# 05_POWER_MCU_1.net
KiCad netlist of a schematic drawn in Altium Designer
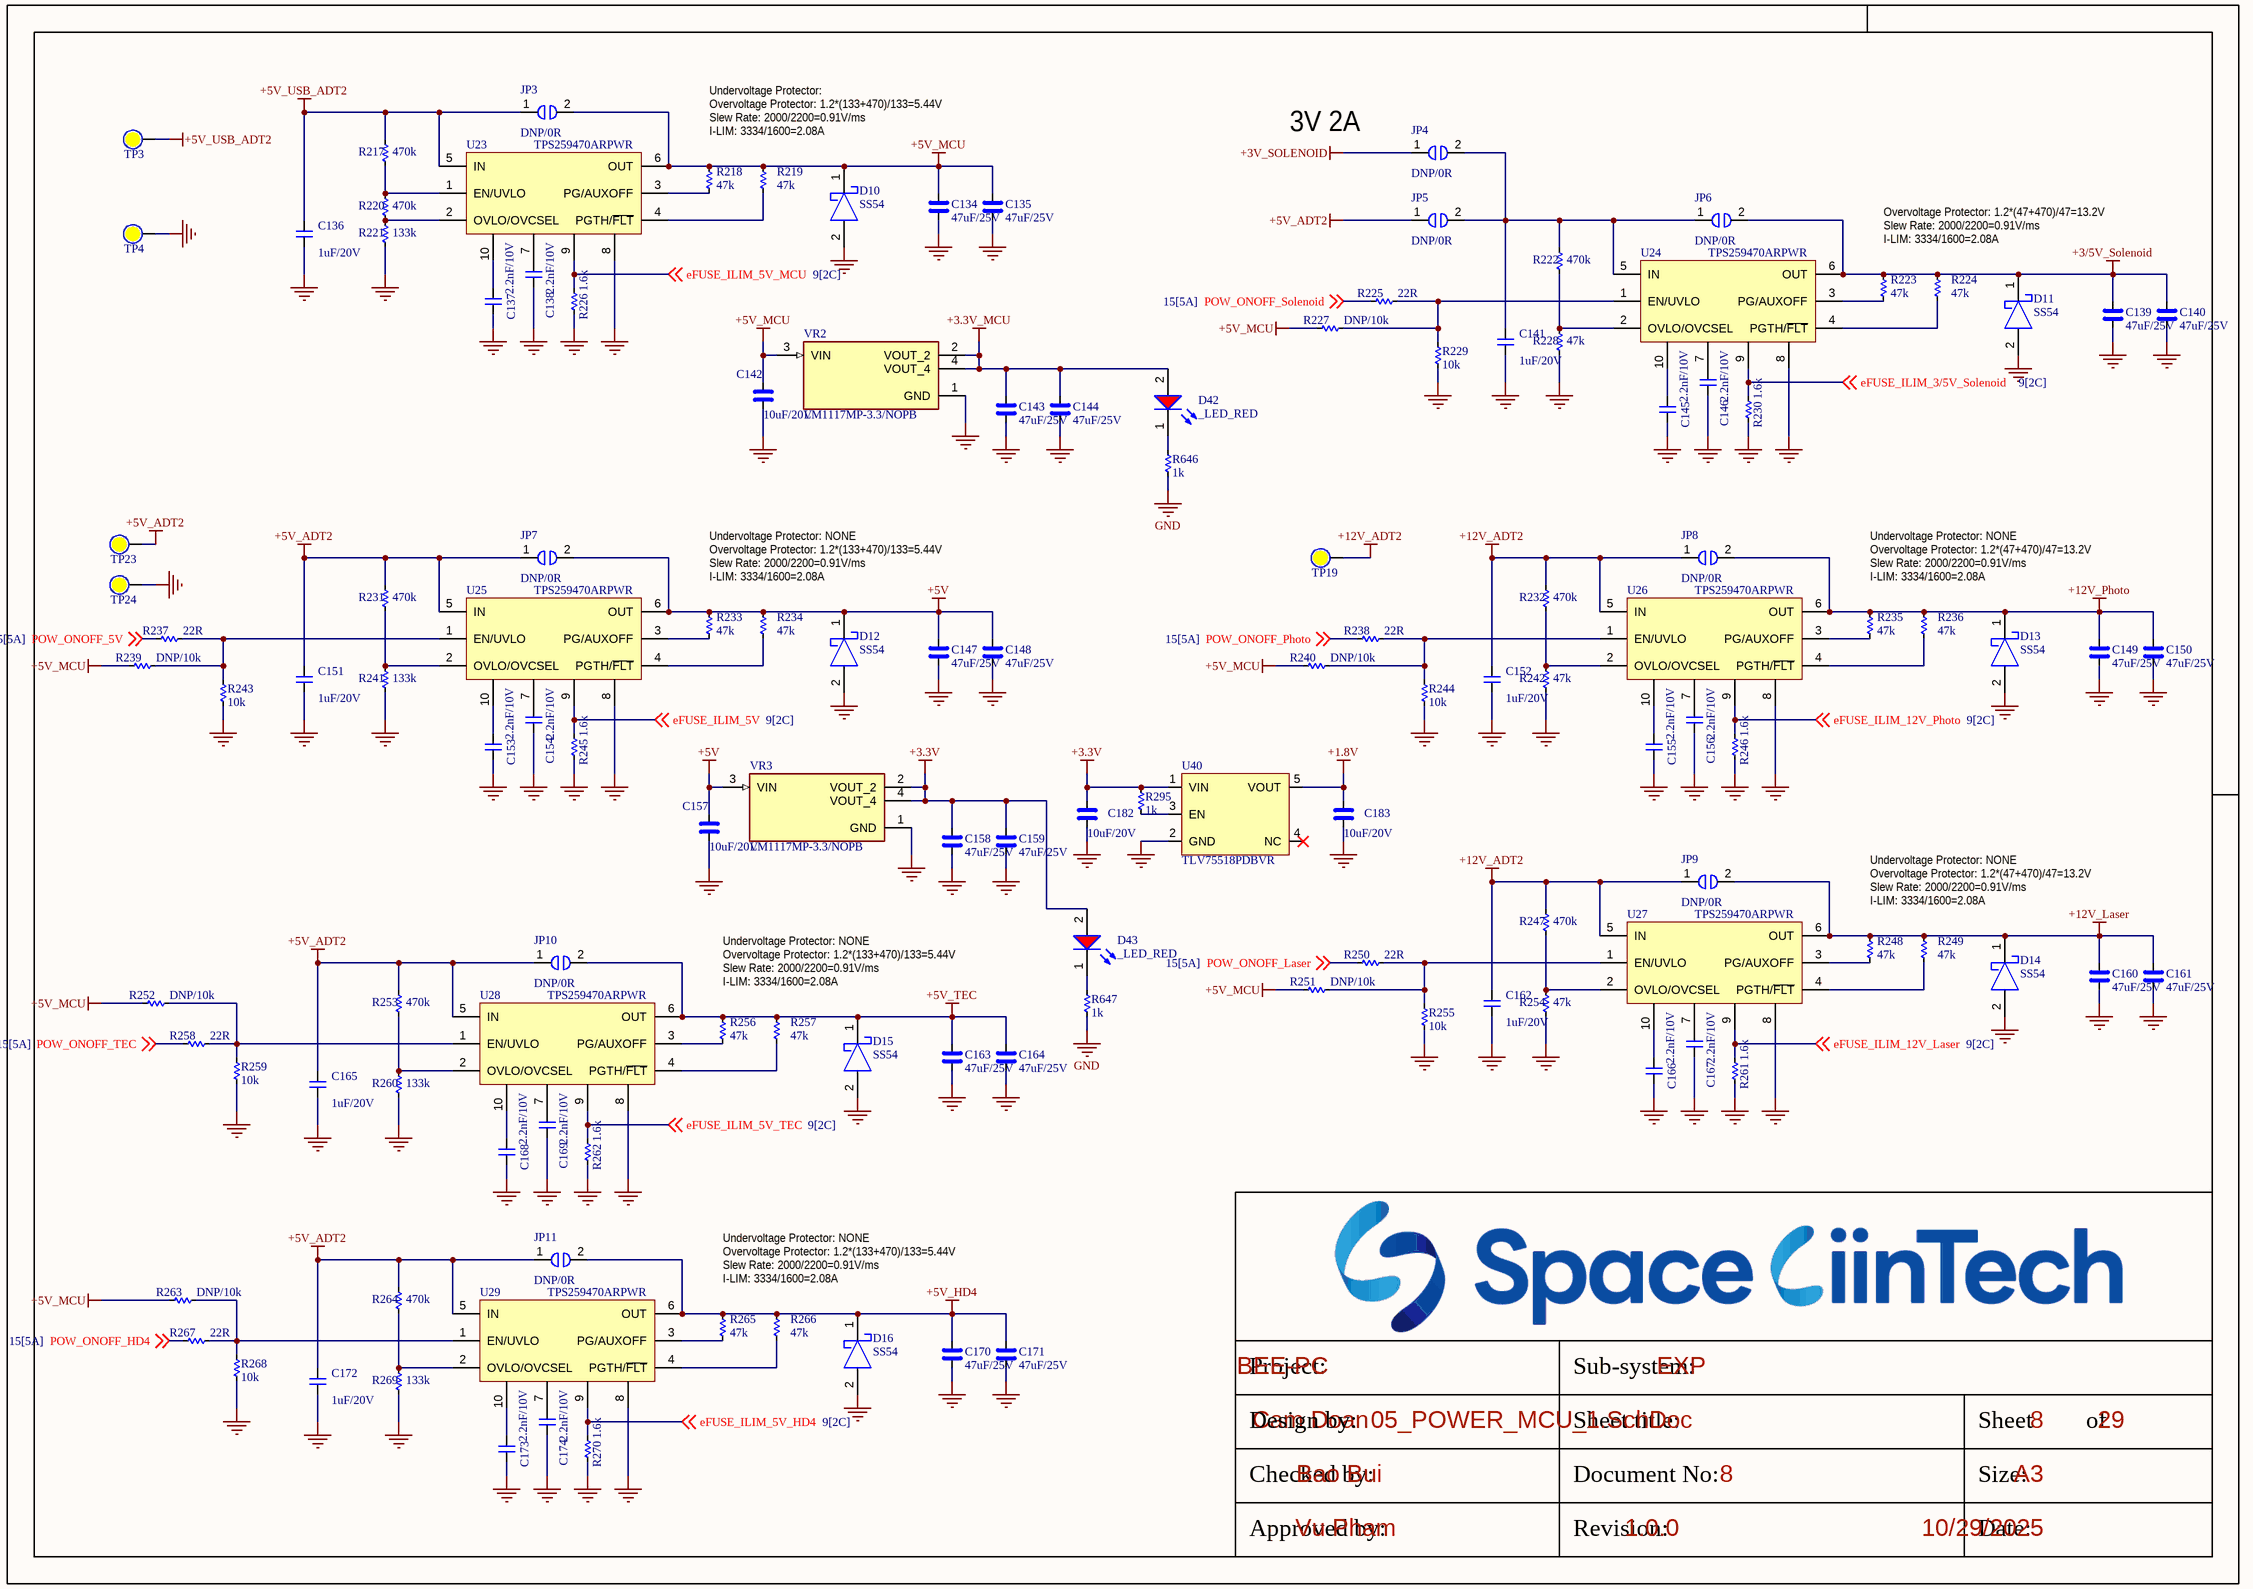
[diagram p0: 05_POWER_MCU_1.SchDoc]

(export (version "E")
  (design (tool "Eeschema 10.0.6"))
  (components
    (comp (ref "C134")
      (value "47uF/25V")
      (footprint "CAP_C_3225X80")
      (description "CAP CHIP High Value")
      (libsource (lib "LABLIB") (part "_CAP_C_High_2"))
    )
    (comp (ref "C135")
      (value "47uF/25V")
      (footprint "CAP_C_3225X80")
      (description "CAP CHIP High Value")
      (libsource (lib "LABLIB") (part "_CAP_C_High_2"))
    )
    (comp (ref "C136")
      (value "1uF/20V")
      (footprint "CAP_C_1005X60")
      (description "CAP CHIP")
      (libsource (lib "LABLIB") (part "_CAP_C_2"))
    )
    (comp (ref "C137")
      (value "2.2nF/10V")
      (footprint "CAP_C_1005X60")
      (description "CAP CHIP")
      (libsource (lib "LABLIB") (part "_CAP_C_2"))
    )
    (comp (ref "C138")
      (value "2.2nF/10V")
      (footprint "CAP_C_1005X60")
      (description "CAP CHIP")
      (libsource (lib "LABLIB") (part "_CAP_C_2"))
    )
    (comp (ref "C139")
      (value "47uF/25V")
      (footprint "CAP_C_3225X80")
      (description "CAP CHIP High Value")
      (libsource (lib "LABLIB") (part "_CAP_C_High_2"))
    )
    (comp (ref "C140")
      (value "47uF/25V")
      (footprint "CAP_C_3225X80")
      (description "CAP CHIP High Value")
      (libsource (lib "LABLIB") (part "_CAP_C_High_2"))
    )
    (comp (ref "C141")
      (value "1uF/20V")
      (footprint "CAP_C_1005X60")
      (description "CAP CHIP")
      (libsource (lib "LABLIB") (part "_CAP_C_2"))
    )
    (comp (ref "C142")
      (value "10uF/20V")
      (footprint "CAP_C_2012X110")
      (description "CAP CHIP High Value")
      (libsource (lib "LABLIB") (part "_CAP_C_High_2"))
    )
    (comp (ref "C143")
      (value "47uF/25V")
      (footprint "CAP_C_3225X80")
      (description "CAP CHIP High Value")
      (libsource (lib "LABLIB") (part "_CAP_C_High_2"))
    )
    (comp (ref "C144")
      (value "47uF/25V")
      (footprint "CAP_C_3225X80")
      (description "CAP CHIP High Value")
      (libsource (lib "LABLIB") (part "_CAP_C_High_2"))
    )
    (comp (ref "C145")
      (value "2.2nF/10V")
      (footprint "CAP_C_1005X60")
      (description "CAP CHIP")
      (libsource (lib "LABLIB") (part "_CAP_C_2"))
    )
    (comp (ref "C146")
      (value "2.2nF/10V")
      (footprint "CAP_C_1005X60")
      (description "CAP CHIP")
      (libsource (lib "LABLIB") (part "_CAP_C_2"))
    )
    (comp (ref "C147")
      (value "47uF/25V")
      (footprint "CAP_C_3225X80")
      (description "CAP CHIP High Value")
      (libsource (lib "LABLIB") (part "_CAP_C_High_2"))
    )
    (comp (ref "C148")
      (value "47uF/25V")
      (footprint "CAP_C_3225X80")
      (description "CAP CHIP High Value")
      (libsource (lib "LABLIB") (part "_CAP_C_High_2"))
    )
    (comp (ref "C149")
      (value "47uF/25V")
      (footprint "CAP_C_3225X80")
      (description "CAP CHIP High Value")
      (libsource (lib "LABLIB") (part "_CAP_C_High_2"))
    )
    (comp (ref "C150")
      (value "47uF/25V")
      (footprint "CAP_C_3225X80")
      (description "CAP CHIP High Value")
      (libsource (lib "LABLIB") (part "_CAP_C_High_2"))
    )
    (comp (ref "C151")
      (value "1uF/20V")
      (footprint "CAP_C_1005X60")
      (description "CAP CHIP")
      (libsource (lib "LABLIB") (part "_CAP_C_2"))
    )
    (comp (ref "C152")
      (value "1uF/20V")
      (footprint "CAP_C_1005X60")
      (description "CAP CHIP")
      (libsource (lib "LABLIB") (part "_CAP_C_2"))
    )
    (comp (ref "C153")
      (value "2.2nF/10V")
      (footprint "CAP_C_1005X60")
      (description "CAP CHIP")
      (libsource (lib "LABLIB") (part "_CAP_C_2"))
    )
    (comp (ref "C154")
      (value "2.2nF/10V")
      (footprint "CAP_C_1005X60")
      (description "CAP CHIP")
      (libsource (lib "LABLIB") (part "_CAP_C_2"))
    )
    (comp (ref "C155")
      (value "2.2nF/10V")
      (footprint "CAP_C_1005X60")
      (description "CAP CHIP")
      (libsource (lib "LABLIB") (part "_CAP_C_2"))
    )
    (comp (ref "C156")
      (value "2.2nF/10V")
      (footprint "CAP_C_1005X60")
      (description "CAP CHIP")
      (libsource (lib "LABLIB") (part "_CAP_C_2"))
    )
    (comp (ref "C157")
      (value "10uF/20V")
      (footprint "CAP_C_2012X110")
      (description "CAP CHIP High Value")
      (libsource (lib "LABLIB") (part "_CAP_C_High_2"))
    )
    (comp (ref "C158")
      (value "47uF/25V")
      (footprint "CAP_C_3225X80")
      (description "CAP CHIP High Value")
      (libsource (lib "LABLIB") (part "_CAP_C_High_2"))
    )
    (comp (ref "C159")
      (value "47uF/25V")
      (footprint "CAP_C_3225X80")
      (description "CAP CHIP High Value")
      (libsource (lib "LABLIB") (part "_CAP_C_High_2"))
    )
    (comp (ref "C160")
      (value "47uF/25V")
      (footprint "CAP_C_3225X80")
      (description "CAP CHIP High Value")
      (libsource (lib "LABLIB") (part "_CAP_C_High_2"))
    )
    (comp (ref "C161")
      (value "47uF/25V")
      (footprint "CAP_C_3225X80")
      (description "CAP CHIP High Value")
      (libsource (lib "LABLIB") (part "_CAP_C_High_2"))
    )
    (comp (ref "C162")
      (value "1uF/20V")
      (footprint "CAP_C_1005X60")
      (description "CAP CHIP")
      (libsource (lib "LABLIB") (part "_CAP_C_2"))
    )
    (comp (ref "C163")
      (value "47uF/25V")
      (footprint "CAP_C_3225X80")
      (description "CAP CHIP High Value")
      (libsource (lib "LABLIB") (part "_CAP_C_High_2"))
    )
    (comp (ref "C164")
      (value "47uF/25V")
      (footprint "CAP_C_3225X80")
      (description "CAP CHIP High Value")
      (libsource (lib "LABLIB") (part "_CAP_C_High_2"))
    )
    (comp (ref "C165")
      (value "1uF/20V")
      (footprint "CAP_C_1005X60")
      (description "CAP CHIP")
      (libsource (lib "LABLIB") (part "_CAP_C_2"))
    )
    (comp (ref "C166")
      (value "2.2nF/10V")
      (footprint "CAP_C_1005X60")
      (description "CAP CHIP")
      (libsource (lib "LABLIB") (part "_CAP_C_2"))
    )
    (comp (ref "C167")
      (value "2.2nF/10V")
      (footprint "CAP_C_1005X60")
      (description "CAP CHIP")
      (libsource (lib "LABLIB") (part "_CAP_C_2"))
    )
    (comp (ref "C168")
      (value "2.2nF/10V")
      (footprint "CAP_C_1005X60")
      (description "CAP CHIP")
      (libsource (lib "LABLIB") (part "_CAP_C_2"))
    )
    (comp (ref "C169")
      (value "2.2nF/10V")
      (footprint "CAP_C_1005X60")
      (description "CAP CHIP")
      (libsource (lib "LABLIB") (part "_CAP_C_2"))
    )
    (comp (ref "C170")
      (value "47uF/25V")
      (footprint "CAP_C_3225X80")
      (description "CAP CHIP High Value")
      (libsource (lib "LABLIB") (part "_CAP_C_High_2"))
    )
    (comp (ref "C171")
      (value "47uF/25V")
      (footprint "CAP_C_3225X80")
      (description "CAP CHIP High Value")
      (libsource (lib "LABLIB") (part "_CAP_C_High_2"))
    )
    (comp (ref "C172")
      (value "1uF/20V")
      (footprint "CAP_C_1005X60")
      (description "CAP CHIP")
      (libsource (lib "LABLIB") (part "_CAP_C_2"))
    )
    (comp (ref "C173")
      (value "2.2nF/10V")
      (footprint "CAP_C_1005X60")
      (description "CAP CHIP")
      (libsource (lib "LABLIB") (part "_CAP_C_2"))
    )
    (comp (ref "C174")
      (value "2.2nF/10V")
      (footprint "CAP_C_1005X60")
      (description "CAP CHIP")
      (libsource (lib "LABLIB") (part "_CAP_C_2"))
    )
    (comp (ref "C182")
      (value "10uF/20V")
      (footprint "CAP_C_2012X110")
      (description "CAP CHIP High Value")
      (libsource (lib "LABLIB") (part "_CAP_C_High_2"))
    )
    (comp (ref "C183")
      (value "10uF/20V")
      (footprint "CAP_C_2012X110")
      (description "CAP CHIP High Value")
      (libsource (lib "LABLIB") (part "_CAP_C_High_2"))
    )
    (comp (ref "D10")
      (value "SS54")
      (footprint "DO-214AC_SMA")
      (description "DIODE SCHOTTKY 60V 3A DO214AA")
      (libsource (lib "EXP_HW_V3") (part "SS54"))
    )
    (comp (ref "D11")
      (value "SS54")
      (footprint "DO-214AC_SMA")
      (description "DIODE SCHOTTKY 60V 3A DO214AA")
      (libsource (lib "EXP_HW_V3") (part "SS54"))
    )
    (comp (ref "D12")
      (value "SS54")
      (footprint "DO-214AC_SMA")
      (description "DIODE SCHOTTKY 60V 3A DO214AA")
      (libsource (lib "EXP_HW_V3") (part "SS54"))
    )
    (comp (ref "D13")
      (value "SS54")
      (footprint "DO-214AC_SMA")
      (description "DIODE SCHOTTKY 60V 3A DO214AA")
      (libsource (lib "EXP_HW_V3") (part "SS54"))
    )
    (comp (ref "D14")
      (value "SS54")
      (footprint "DO-214AC_SMA")
      (description "DIODE SCHOTTKY 60V 3A DO214AA")
      (libsource (lib "EXP_HW_V3") (part "SS54"))
    )
    (comp (ref "D15")
      (value "SS54")
      (footprint "DO-214AC_SMA")
      (description "DIODE SCHOTTKY 60V 3A DO214AA")
      (libsource (lib "EXP_HW_V3") (part "SS54"))
    )
    (comp (ref "D16")
      (value "SS54")
      (footprint "DO-214AC_SMA")
      (description "DIODE SCHOTTKY 60V 3A DO214AA")
      (libsource (lib "EXP_HW_V3") (part "SS54"))
    )
    (comp (ref "D42") (value "_LED_RED") (footprint "LED_0603") (libsource (lib "LABLIB") (part "_LED_RED")))
    (comp (ref "D43") (value "_LED_RED") (footprint "LED_0603") (libsource (lib "LABLIB") (part "_LED_RED")))
    (comp (ref "JP3")
      (value "DNP/0R")
      (footprint "RES_C_1608X60")
      (libsource (lib "LABLIB") (part "JUMPER_1_1"))
    )
    (comp (ref "JP4")
      (value "DNP/0R")
      (footprint "RES_C_1608X60")
      (libsource (lib "LABLIB") (part "JUMPER_1_1"))
    )
    (comp (ref "JP5")
      (value "DNP/0R")
      (footprint "RES_C_1608X60")
      (libsource (lib "LABLIB") (part "JUMPER_1_1"))
    )
    (comp (ref "JP6")
      (value "DNP/0R")
      (footprint "RES_C_1608X60")
      (libsource (lib "LABLIB") (part "JUMPER_1_1"))
    )
    (comp (ref "JP7")
      (value "DNP/0R")
      (footprint "RES_C_1608X60")
      (libsource (lib "LABLIB") (part "JUMPER_1_1"))
    )
    (comp (ref "JP8")
      (value "DNP/0R")
      (footprint "RES_C_1608X60")
      (libsource (lib "LABLIB") (part "JUMPER_1_1"))
    )
    (comp (ref "JP9")
      (value "DNP/0R")
      (footprint "RES_C_1608X60")
      (libsource (lib "LABLIB") (part "JUMPER_1_1"))
    )
    (comp (ref "JP10")
      (value "DNP/0R")
      (footprint "RES_C_1608X60")
      (libsource (lib "LABLIB") (part "JUMPER_1_1"))
    )
    (comp (ref "JP11")
      (value "DNP/0R")
      (footprint "RES_C_1608X60")
      (libsource (lib "LABLIB") (part "JUMPER_1_1"))
    )
    (comp (ref "R217")
      (value "470k")
      (footprint "RES_C_1005X40")
      (description "RES")
      (libsource (lib "LABLIB") (part "_RES_B_2"))
    )
    (comp (ref "R218")
      (value "47k")
      (footprint "RES_C_1005X40")
      (description "RES")
      (libsource (lib "LABLIB") (part "_RES_B_2"))
    )
    (comp (ref "R219")
      (value "47k")
      (footprint "RES_C_1005X40")
      (description "RES")
      (libsource (lib "LABLIB") (part "_RES_B_2"))
    )
    (comp (ref "R220")
      (value "470k")
      (footprint "RES_C_1005X40")
      (description "RES")
      (libsource (lib "LABLIB") (part "_RES_B_2"))
    )
    (comp (ref "R221")
      (value "133k")
      (footprint "RES_C_1005X40")
      (description "RES")
      (libsource (lib "LABLIB") (part "_RES_B_2"))
    )
    (comp (ref "R222")
      (value "470k")
      (footprint "RES_C_1005X40")
      (description "RES")
      (libsource (lib "LABLIB") (part "_RES_B_2"))
    )
    (comp (ref "R223")
      (value "47k")
      (footprint "RES_C_1005X40")
      (description "RES")
      (libsource (lib "LABLIB") (part "_RES_B_2"))
    )
    (comp (ref "R224")
      (value "47k")
      (footprint "RES_C_1005X40")
      (description "RES")
      (libsource (lib "LABLIB") (part "_RES_B_2"))
    )
    (comp (ref "R225")
      (value "22R")
      (footprint "RES_C_1005X40")
      (description "RES")
      (libsource (lib "LABLIB") (part "_RES_B_2"))
    )
    (comp (ref "R226")
      (value "1.6k")
      (footprint "RES_C_1005X40")
      (description "RES")
      (libsource (lib "LABLIB") (part "_RES_B_2"))
    )
    (comp (ref "R227")
      (value "DNP/10k")
      (footprint "RES_C_1005X40")
      (description "RES")
      (libsource (lib "LABLIB") (part "_RES_B_2"))
    )
    (comp (ref "R228")
      (value "47k")
      (footprint "RES_C_1005X40")
      (description "RES")
      (libsource (lib "LABLIB") (part "_RES_B_2"))
    )
    (comp (ref "R229")
      (value "10k")
      (footprint "RES_C_1005X40")
      (description "RES")
      (libsource (lib "LABLIB") (part "_RES_B_2"))
    )
    (comp (ref "R230")
      (value "1.6k")
      (footprint "RES_C_1005X40")
      (description "RES")
      (libsource (lib "LABLIB") (part "_RES_B_2"))
    )
    (comp (ref "R231")
      (value "470k")
      (footprint "RES_C_1005X40")
      (description "RES")
      (libsource (lib "LABLIB") (part "_RES_B_2"))
    )
    (comp (ref "R232")
      (value "470k")
      (footprint "RES_C_1005X40")
      (description "RES")
      (libsource (lib "LABLIB") (part "_RES_B_2"))
    )
    (comp (ref "R233")
      (value "47k")
      (footprint "RES_C_1005X40")
      (description "RES")
      (libsource (lib "LABLIB") (part "_RES_B_2"))
    )
    (comp (ref "R234")
      (value "47k")
      (footprint "RES_C_1005X40")
      (description "RES")
      (libsource (lib "LABLIB") (part "_RES_B_2"))
    )
    (comp (ref "R235")
      (value "47k")
      (footprint "RES_C_1005X40")
      (description "RES")
      (libsource (lib "LABLIB") (part "_RES_B_2"))
    )
    (comp (ref "R236")
      (value "47k")
      (footprint "RES_C_1005X40")
      (description "RES")
      (libsource (lib "LABLIB") (part "_RES_B_2"))
    )
    (comp (ref "R237")
      (value "22R")
      (footprint "RES_C_1005X40")
      (description "RES")
      (libsource (lib "LABLIB") (part "_RES_B_2"))
    )
    (comp (ref "R238")
      (value "22R")
      (footprint "RES_C_1005X40")
      (description "RES")
      (libsource (lib "LABLIB") (part "_RES_B_2"))
    )
    (comp (ref "R239")
      (value "DNP/10k")
      (footprint "RES_C_1005X40")
      (description "RES")
      (libsource (lib "LABLIB") (part "_RES_B_2"))
    )
    (comp (ref "R240")
      (value "DNP/10k")
      (footprint "RES_C_1005X40")
      (description "RES")
      (libsource (lib "LABLIB") (part "_RES_B_2"))
    )
    (comp (ref "R241")
      (value "133k")
      (footprint "RES_C_1005X40")
      (description "RES")
      (libsource (lib "LABLIB") (part "_RES_B_2"))
    )
    (comp (ref "R242")
      (value "47k")
      (footprint "RES_C_1005X40")
      (description "RES")
      (libsource (lib "LABLIB") (part "_RES_B_2"))
    )
    (comp (ref "R243")
      (value "10k")
      (footprint "RES_C_1005X40")
      (description "RES")
      (libsource (lib "LABLIB") (part "_RES_B_2"))
    )
    (comp (ref "R244")
      (value "10k")
      (footprint "RES_C_1005X40")
      (description "RES")
      (libsource (lib "LABLIB") (part "_RES_B_2"))
    )
    (comp (ref "R245")
      (value "1.6k")
      (footprint "RES_C_1005X40")
      (description "RES")
      (libsource (lib "LABLIB") (part "_RES_B_2"))
    )
    (comp (ref "R246")
      (value "1.6k")
      (footprint "RES_C_1005X40")
      (description "RES")
      (libsource (lib "LABLIB") (part "_RES_B_2"))
    )
    (comp (ref "R247")
      (value "470k")
      (footprint "RES_C_1005X40")
      (description "RES")
      (libsource (lib "LABLIB") (part "_RES_B_2"))
    )
    (comp (ref "R248")
      (value "47k")
      (footprint "RES_C_1005X40")
      (description "RES")
      (libsource (lib "LABLIB") (part "_RES_B_2"))
    )
    (comp (ref "R249")
      (value "47k")
      (footprint "RES_C_1005X40")
      (description "RES")
      (libsource (lib "LABLIB") (part "_RES_B_2"))
    )
    (comp (ref "R250")
      (value "22R")
      (footprint "RES_C_1005X40")
      (description "RES")
      (libsource (lib "LABLIB") (part "_RES_B_2"))
    )
    (comp (ref "R251")
      (value "DNP/10k")
      (footprint "RES_C_1005X40")
      (description "RES")
      (libsource (lib "LABLIB") (part "_RES_B_2"))
    )
    (comp (ref "R252")
      (value "DNP/10k")
      (footprint "RES_C_1005X40")
      (description "RES")
      (libsource (lib "LABLIB") (part "_RES_B_2"))
    )
    (comp (ref "R253")
      (value "470k")
      (footprint "RES_C_1005X40")
      (description "RES")
      (libsource (lib "LABLIB") (part "_RES_B_2"))
    )
    (comp (ref "R254")
      (value "47k")
      (footprint "RES_C_1005X40")
      (description "RES")
      (libsource (lib "LABLIB") (part "_RES_B_2"))
    )
    (comp (ref "R255")
      (value "10k")
      (footprint "RES_C_1005X40")
      (description "RES")
      (libsource (lib "LABLIB") (part "_RES_B_2"))
    )
    (comp (ref "R256")
      (value "47k")
      (footprint "RES_C_1005X40")
      (description "RES")
      (libsource (lib "LABLIB") (part "_RES_B_2"))
    )
    (comp (ref "R257")
      (value "47k")
      (footprint "RES_C_1005X40")
      (description "RES")
      (libsource (lib "LABLIB") (part "_RES_B_2"))
    )
    (comp (ref "R258")
      (value "22R")
      (footprint "RES_C_1005X40")
      (description "RES")
      (libsource (lib "LABLIB") (part "_RES_B_2"))
    )
    (comp (ref "R259")
      (value "10k")
      (footprint "RES_C_1005X40")
      (description "RES")
      (libsource (lib "LABLIB") (part "_RES_B_2"))
    )
    (comp (ref "R260")
      (value "133k")
      (footprint "RES_C_1005X40")
      (description "RES")
      (libsource (lib "LABLIB") (part "_RES_B_2"))
    )
    (comp (ref "R261")
      (value "1.6k")
      (footprint "RES_C_1005X40")
      (description "RES")
      (libsource (lib "LABLIB") (part "_RES_B_2"))
    )
    (comp (ref "R262")
      (value "1.6k")
      (footprint "RES_C_1005X40")
      (description "RES")
      (libsource (lib "LABLIB") (part "_RES_B_2"))
    )
    (comp (ref "R263")
      (value "DNP/10k")
      (footprint "RES_C_1005X40")
      (description "RES")
      (libsource (lib "LABLIB") (part "_RES_B_2"))
    )
    (comp (ref "R264")
      (value "470k")
      (footprint "RES_C_1005X40")
      (description "RES")
      (libsource (lib "LABLIB") (part "_RES_B_2"))
    )
    (comp (ref "R265")
      (value "47k")
      (footprint "RES_C_1005X40")
      (description "RES")
      (libsource (lib "LABLIB") (part "_RES_B_2"))
    )
    (comp (ref "R266")
      (value "47k")
      (footprint "RES_C_1005X40")
      (description "RES")
      (libsource (lib "LABLIB") (part "_RES_B_2"))
    )
    (comp (ref "R267")
      (value "22R")
      (footprint "RES_C_1005X40")
      (description "RES")
      (libsource (lib "LABLIB") (part "_RES_B_2"))
    )
    (comp (ref "R268")
      (value "10k")
      (footprint "RES_C_1005X40")
      (description "RES")
      (libsource (lib "LABLIB") (part "_RES_B_2"))
    )
    (comp (ref "R269")
      (value "133k")
      (footprint "RES_C_1005X40")
      (description "RES")
      (libsource (lib "LABLIB") (part "_RES_B_2"))
    )
    (comp (ref "R270")
      (value "1.6k")
      (footprint "RES_C_1005X40")
      (description "RES")
      (libsource (lib "LABLIB") (part "_RES_B_2"))
    )
    (comp (ref "R295")
      (value "1k")
      (footprint "RES_C_1005X40")
      (description "RES")
      (libsource (lib "LABLIB") (part "_RES_B_2"))
    )
    (comp (ref "R646")
      (value "1k")
      (footprint "RES_C_1005X40")
      (description "RES")
      (libsource (lib "LABLIB") (part "_RES_B_2"))
    )
    (comp (ref "R647")
      (value "1k")
      (footprint "RES_C_1005X40")
      (description "RES")
      (libsource (lib "LABLIB") (part "_RES_B_2"))
    )
    (comp (ref "TP3")
      (value "~")
      (footprint "Testpoint_TH_D130H80")
      (description "Test Point")
      (libsource (lib "LABLIB") (part "Test Point"))
    )
    (comp (ref "TP4")
      (value "~")
      (footprint "Testpoint_TH_D130H80")
      (description "Test Point")
      (libsource (lib "LABLIB") (part "Test Point"))
    )
    (comp (ref "TP19")
      (value "~")
      (footprint "Testpoint_TH_D130H80")
      (description "Test Point")
      (libsource (lib "LABLIB") (part "Test Point"))
    )
    (comp (ref "TP23")
      (value "~")
      (footprint "Testpoint_TH_D130H80")
      (description "Test Point")
      (libsource (lib "LABLIB") (part "Test Point"))
    )
    (comp (ref "TP24")
      (value "~")
      (footprint "Testpoint_TH_D130H80")
      (description "Test Point")
      (libsource (lib "LABLIB") (part "Test Point"))
    )
    (comp (ref "U23")
      (value "TPS259470ARPWR")
      (footprint "VQFN-HR-10")
      (libsource (lib "EXP_HW_V3") (part "TPS259470ARPWR"))
    )
    (comp (ref "U24")
      (value "TPS259470ARPWR")
      (footprint "VQFN-HR-10")
      (libsource (lib "EXP_HW_V3") (part "TPS259470ARPWR"))
    )
    (comp (ref "U25")
      (value "TPS259470ARPWR")
      (footprint "VQFN-HR-10")
      (libsource (lib "EXP_HW_V3") (part "TPS259470ARPWR"))
    )
    (comp (ref "U26")
      (value "TPS259470ARPWR")
      (footprint "VQFN-HR-10")
      (libsource (lib "EXP_HW_V3") (part "TPS259470ARPWR"))
    )
    (comp (ref "U27")
      (value "TPS259470ARPWR")
      (footprint "VQFN-HR-10")
      (libsource (lib "EXP_HW_V3") (part "TPS259470ARPWR"))
    )
    (comp (ref "U28")
      (value "TPS259470ARPWR")
      (footprint "VQFN-HR-10")
      (libsource (lib "EXP_HW_V3") (part "TPS259470ARPWR"))
    )
    (comp (ref "U29")
      (value "TPS259470ARPWR")
      (footprint "VQFN-HR-10")
      (libsource (lib "EXP_HW_V3") (part "TPS259470ARPWR"))
    )
    (comp (ref "U40")
      (value "TLV75518PDBVR")
      (footprint "SOT25")
      (libsource (lib "CAMERA_SchLib") (part "IC_POWER_AP7347DQ"))
    )
    (comp (ref "VR2")
      (value "LM1117MP-3.3/NOPB")
      (footprint "VREG_LM1117MP-3.3/NOPB")
      (description "800-mA 15-V linear voltage regulator")
      (fields (field (name "MF") "Texas Instruments"))
      (libsource (lib "new_component") (part "LM1117MP-3.3/NOPB"))
    )
    (comp (ref "VR3")
      (value "LM1117MP-3.3/NOPB")
      (footprint "VREG_LM1117MP-3.3/NOPB")
      (description "800-mA 15-V linear voltage regulator")
      (fields (field (name "MF") "Texas Instruments"))
      (libsource (lib "new_component") (part "LM1117MP-3.3/NOPB"))
    )
  )
  (nets
    (net (code "1") (name "+1.8V") (class "Default")
      (node (ref "C183") (pin "1") (pinfunction "1_1") (pintype "passive"))
      (node (ref "U40") (pin "5") (pinfunction "VOUT_5") (pintype "passive"))
    )
    (net (code "2") (name "+3.3V") (class "Default")
      (node (ref "C158") (pin "2") (pinfunction "2_2") (pintype "passive"))
      (node (ref "C159") (pin "2") (pinfunction "2_2") (pintype "passive"))
      (node (ref "C182") (pin "1") (pinfunction "1_1") (pintype "passive"))
      (node (ref "D43") (pin "2") (pinfunction "A_2") (pintype "passive"))
      (node (ref "R295") (pin "2") (pinfunction "2_2") (pintype "passive"))
      (node (ref "U40") (pin "1") (pinfunction "VIN_1") (pintype "passive"))
      (node (ref "VR3") (pin "2") (pinfunction "VOUT_2_2") (pintype "power_in"))
      (node (ref "VR3") (pin "4") (pinfunction "VOUT_4_4") (pintype "power_in"))
    )
    (net (code "3") (name "+3.3V_MCU") (class "Default")
      (node (ref "C143") (pin "2") (pinfunction "2_2") (pintype "passive"))
      (node (ref "C144") (pin "2") (pinfunction "2_2") (pintype "passive"))
      (node (ref "D42") (pin "2") (pinfunction "A_2") (pintype "passive"))
      (node (ref "VR2") (pin "2") (pinfunction "VOUT_2_2") (pintype "power_in"))
      (node (ref "VR2") (pin "4") (pinfunction "VOUT_4_4") (pintype "power_in"))
    )
    (net (code "4") (name "+3V_SOLENOID") (class "Default")
      (node (ref "JP4") (pin "1") (pinfunction "1_1") (pintype "passive"))
    )
    (net (code "5") (name "+3{slash}5V_Solenoid") (class "Default")
      (node (ref "C139") (pin "2") (pinfunction "2_2") (pintype "passive"))
      (node (ref "C140") (pin "2") (pinfunction "2_2") (pintype "passive"))
      (node (ref "D11") (pin "1") (pinfunction "1_1") (pintype "passive"))
      (node (ref "JP6") (pin "2") (pinfunction "2_2") (pintype "passive"))
      (node (ref "R223") (pin "2") (pinfunction "2_2") (pintype "passive"))
      (node (ref "R224") (pin "2") (pinfunction "2_2") (pintype "passive"))
      (node (ref "U24") (pin "6") (pinfunction "OUT_6") (pintype "passive"))
    )
    (net (code "6") (name "+5V") (class "Default")
      (node (ref "C147") (pin "2") (pinfunction "2_2") (pintype "passive"))
      (node (ref "C148") (pin "2") (pinfunction "2_2") (pintype "passive"))
      (node (ref "C157") (pin "1") (pinfunction "1_1") (pintype "passive"))
      (node (ref "D12") (pin "1") (pinfunction "1_1") (pintype "passive"))
      (node (ref "JP7") (pin "2") (pinfunction "2_2") (pintype "passive"))
      (node (ref "R233") (pin "2") (pinfunction "2_2") (pintype "passive"))
      (node (ref "R234") (pin "2") (pinfunction "2_2") (pintype "passive"))
      (node (ref "U25") (pin "6") (pinfunction "OUT_6") (pintype "passive"))
      (node (ref "VR3") (pin "3") (pinfunction "VIN_3") (pintype "input"))
    )
    (net (code "7") (name "+5V_ADT2") (class "Default")
      (node (ref "C151") (pin "2") (pinfunction "2_2") (pintype "passive"))
      (node (ref "C165") (pin "2") (pinfunction "2_2") (pintype "passive"))
      (node (ref "C172") (pin "2") (pinfunction "2_2") (pintype "passive"))
      (node (ref "JP10") (pin "1") (pinfunction "1_1") (pintype "passive"))
      (node (ref "JP11") (pin "1") (pinfunction "1_1") (pintype "passive"))
      (node (ref "JP5") (pin "1") (pinfunction "1_1") (pintype "passive"))
      (node (ref "JP7") (pin "1") (pinfunction "1_1") (pintype "passive"))
      (node (ref "R231") (pin "2") (pinfunction "2_2") (pintype "passive"))
      (node (ref "R253") (pin "2") (pinfunction "2_2") (pintype "passive"))
      (node (ref "R264") (pin "2") (pinfunction "2_2") (pintype "passive"))
      (node (ref "TP23") (pin "1") (pinfunction "1_1") (pintype "passive"))
      (node (ref "U25") (pin "5") (pinfunction "IN_5") (pintype "passive"))
      (node (ref "U28") (pin "5") (pinfunction "IN_5") (pintype "passive"))
      (node (ref "U29") (pin "5") (pinfunction "IN_5") (pintype "passive"))
    )
    (net (code "8") (name "+5V_HD4") (class "Default")
      (node (ref "C170") (pin "2") (pinfunction "2_2") (pintype "passive"))
      (node (ref "C171") (pin "2") (pinfunction "2_2") (pintype "passive"))
      (node (ref "D16") (pin "1") (pinfunction "1_1") (pintype "passive"))
      (node (ref "JP11") (pin "2") (pinfunction "2_2") (pintype "passive"))
      (node (ref "R265") (pin "2") (pinfunction "2_2") (pintype "passive"))
      (node (ref "R266") (pin "2") (pinfunction "2_2") (pintype "passive"))
      (node (ref "U29") (pin "6") (pinfunction "OUT_6") (pintype "passive"))
    )
    (net (code "9") (name "+5V_MCU") (class "Default")
      (node (ref "C134") (pin "2") (pinfunction "2_2") (pintype "passive"))
      (node (ref "C135") (pin "2") (pinfunction "2_2") (pintype "passive"))
      (node (ref "C142") (pin "1") (pinfunction "1_1") (pintype "passive"))
      (node (ref "D10") (pin "1") (pinfunction "1_1") (pintype "passive"))
      (node (ref "JP3") (pin "2") (pinfunction "2_2") (pintype "passive"))
      (node (ref "R218") (pin "2") (pinfunction "2_2") (pintype "passive"))
      (node (ref "R219") (pin "2") (pinfunction "2_2") (pintype "passive"))
      (node (ref "R227") (pin "2") (pinfunction "2_2") (pintype "passive"))
      (node (ref "R239") (pin "2") (pinfunction "2_2") (pintype "passive"))
      (node (ref "R240") (pin "2") (pinfunction "2_2") (pintype "passive"))
      (node (ref "R251") (pin "2") (pinfunction "2_2") (pintype "passive"))
      (node (ref "R252") (pin "2") (pinfunction "2_2") (pintype "passive"))
      (node (ref "R263") (pin "2") (pinfunction "2_2") (pintype "passive"))
      (node (ref "U23") (pin "6") (pinfunction "OUT_6") (pintype "passive"))
      (node (ref "VR2") (pin "3") (pinfunction "VIN_3") (pintype "input"))
    )
    (net (code "10") (name "+5V_TEC") (class "Default")
      (node (ref "C163") (pin "2") (pinfunction "2_2") (pintype "passive"))
      (node (ref "C164") (pin "2") (pinfunction "2_2") (pintype "passive"))
      (node (ref "D15") (pin "1") (pinfunction "1_1") (pintype "passive"))
      (node (ref "JP10") (pin "2") (pinfunction "2_2") (pintype "passive"))
      (node (ref "R256") (pin "2") (pinfunction "2_2") (pintype "passive"))
      (node (ref "R257") (pin "2") (pinfunction "2_2") (pintype "passive"))
      (node (ref "U28") (pin "6") (pinfunction "OUT_6") (pintype "passive"))
    )
    (net (code "11") (name "+5V_USB_ADT2") (class "Default")
      (node (ref "C136") (pin "2") (pinfunction "2_2") (pintype "passive"))
      (node (ref "JP3") (pin "1") (pinfunction "1_1") (pintype "passive"))
      (node (ref "R217") (pin "2") (pinfunction "2_2") (pintype "passive"))
      (node (ref "TP3") (pin "1") (pinfunction "1_1") (pintype "passive"))
      (node (ref "U23") (pin "5") (pinfunction "IN_5") (pintype "passive"))
    )
    (net (code "12") (name "+12V_ADT2") (class "Default")
      (node (ref "C152") (pin "2") (pinfunction "2_2") (pintype "passive"))
      (node (ref "C162") (pin "2") (pinfunction "2_2") (pintype "passive"))
      (node (ref "JP8") (pin "1") (pinfunction "1_1") (pintype "passive"))
      (node (ref "JP9") (pin "1") (pinfunction "1_1") (pintype "passive"))
      (node (ref "R232") (pin "2") (pinfunction "2_2") (pintype "passive"))
      (node (ref "R247") (pin "2") (pinfunction "2_2") (pintype "passive"))
      (node (ref "TP19") (pin "1") (pinfunction "1_1") (pintype "passive"))
      (node (ref "U26") (pin "5") (pinfunction "IN_5") (pintype "passive"))
      (node (ref "U27") (pin "5") (pinfunction "IN_5") (pintype "passive"))
    )
    (net (code "13") (name "+12V_Laser") (class "Default")
      (node (ref "C160") (pin "2") (pinfunction "2_2") (pintype "passive"))
      (node (ref "C161") (pin "2") (pinfunction "2_2") (pintype "passive"))
      (node (ref "D14") (pin "1") (pinfunction "1_1") (pintype "passive"))
      (node (ref "JP9") (pin "2") (pinfunction "2_2") (pintype "passive"))
      (node (ref "R248") (pin "2") (pinfunction "2_2") (pintype "passive"))
      (node (ref "R249") (pin "2") (pinfunction "2_2") (pintype "passive"))
      (node (ref "U27") (pin "6") (pinfunction "OUT_6") (pintype "passive"))
    )
    (net (code "14") (name "+12V_Photo") (class "Default")
      (node (ref "C149") (pin "2") (pinfunction "2_2") (pintype "passive"))
      (node (ref "C150") (pin "2") (pinfunction "2_2") (pintype "passive"))
      (node (ref "D13") (pin "1") (pinfunction "1_1") (pintype "passive"))
      (node (ref "JP8") (pin "2") (pinfunction "2_2") (pintype "passive"))
      (node (ref "R235") (pin "2") (pinfunction "2_2") (pintype "passive"))
      (node (ref "R236") (pin "2") (pinfunction "2_2") (pintype "passive"))
      (node (ref "U26") (pin "6") (pinfunction "OUT_6") (pintype "passive"))
    )
    (net (code "15") (name "GND") (class "Default")
      (node (ref "C134") (pin "1") (pinfunction "1_1") (pintype "passive"))
      (node (ref "C135") (pin "1") (pinfunction "1_1") (pintype "passive"))
      (node (ref "C136") (pin "1") (pinfunction "1_1") (pintype "passive"))
      (node (ref "C137") (pin "1") (pinfunction "1_1") (pintype "passive"))
      (node (ref "C138") (pin "1") (pinfunction "1_1") (pintype "passive"))
      (node (ref "C139") (pin "1") (pinfunction "1_1") (pintype "passive"))
      (node (ref "C140") (pin "1") (pinfunction "1_1") (pintype "passive"))
      (node (ref "C141") (pin "1") (pinfunction "1_1") (pintype "passive"))
      (node (ref "C142") (pin "2") (pinfunction "2_2") (pintype "passive"))
      (node (ref "C143") (pin "1") (pinfunction "1_1") (pintype "passive"))
      (node (ref "C144") (pin "1") (pinfunction "1_1") (pintype "passive"))
      (node (ref "C145") (pin "1") (pinfunction "1_1") (pintype "passive"))
      (node (ref "C146") (pin "1") (pinfunction "1_1") (pintype "passive"))
      (node (ref "C147") (pin "1") (pinfunction "1_1") (pintype "passive"))
      (node (ref "C148") (pin "1") (pinfunction "1_1") (pintype "passive"))
      (node (ref "C149") (pin "1") (pinfunction "1_1") (pintype "passive"))
      (node (ref "C150") (pin "1") (pinfunction "1_1") (pintype "passive"))
      (node (ref "C151") (pin "1") (pinfunction "1_1") (pintype "passive"))
      (node (ref "C152") (pin "1") (pinfunction "1_1") (pintype "passive"))
      (node (ref "C153") (pin "1") (pinfunction "1_1") (pintype "passive"))
      (node (ref "C154") (pin "1") (pinfunction "1_1") (pintype "passive"))
      (node (ref "C155") (pin "1") (pinfunction "1_1") (pintype "passive"))
      (node (ref "C156") (pin "1") (pinfunction "1_1") (pintype "passive"))
      (node (ref "C157") (pin "2") (pinfunction "2_2") (pintype "passive"))
      (node (ref "C158") (pin "1") (pinfunction "1_1") (pintype "passive"))
      (node (ref "C159") (pin "1") (pinfunction "1_1") (pintype "passive"))
      (node (ref "C160") (pin "1") (pinfunction "1_1") (pintype "passive"))
      (node (ref "C161") (pin "1") (pinfunction "1_1") (pintype "passive"))
      (node (ref "C162") (pin "1") (pinfunction "1_1") (pintype "passive"))
      (node (ref "C163") (pin "1") (pinfunction "1_1") (pintype "passive"))
      (node (ref "C164") (pin "1") (pinfunction "1_1") (pintype "passive"))
      (node (ref "C165") (pin "1") (pinfunction "1_1") (pintype "passive"))
      (node (ref "C166") (pin "1") (pinfunction "1_1") (pintype "passive"))
      (node (ref "C167") (pin "1") (pinfunction "1_1") (pintype "passive"))
      (node (ref "C168") (pin "1") (pinfunction "1_1") (pintype "passive"))
      (node (ref "C169") (pin "1") (pinfunction "1_1") (pintype "passive"))
      (node (ref "C170") (pin "1") (pinfunction "1_1") (pintype "passive"))
      (node (ref "C171") (pin "1") (pinfunction "1_1") (pintype "passive"))
      (node (ref "C172") (pin "1") (pinfunction "1_1") (pintype "passive"))
      (node (ref "C173") (pin "1") (pinfunction "1_1") (pintype "passive"))
      (node (ref "C174") (pin "1") (pinfunction "1_1") (pintype "passive"))
      (node (ref "C182") (pin "2") (pinfunction "2_2") (pintype "passive"))
      (node (ref "C183") (pin "2") (pinfunction "2_2") (pintype "passive"))
      (node (ref "D10") (pin "2") (pinfunction "2_2") (pintype "passive"))
      (node (ref "D11") (pin "2") (pinfunction "2_2") (pintype "passive"))
      (node (ref "D12") (pin "2") (pinfunction "2_2") (pintype "passive"))
      (node (ref "D13") (pin "2") (pinfunction "2_2") (pintype "passive"))
      (node (ref "D14") (pin "2") (pinfunction "2_2") (pintype "passive"))
      (node (ref "D15") (pin "2") (pinfunction "2_2") (pintype "passive"))
      (node (ref "D16") (pin "2") (pinfunction "2_2") (pintype "passive"))
      (node (ref "R221") (pin "1") (pinfunction "1_1") (pintype "passive"))
      (node (ref "R226") (pin "1") (pinfunction "1_1") (pintype "passive"))
      (node (ref "R228") (pin "1") (pinfunction "1_1") (pintype "passive"))
      (node (ref "R229") (pin "2") (pinfunction "2_2") (pintype "passive"))
      (node (ref "R230") (pin "1") (pinfunction "1_1") (pintype "passive"))
      (node (ref "R241") (pin "1") (pinfunction "1_1") (pintype "passive"))
      (node (ref "R242") (pin "1") (pinfunction "1_1") (pintype "passive"))
      (node (ref "R243") (pin "2") (pinfunction "2_2") (pintype "passive"))
      (node (ref "R244") (pin "2") (pinfunction "2_2") (pintype "passive"))
      (node (ref "R245") (pin "1") (pinfunction "1_1") (pintype "passive"))
      (node (ref "R246") (pin "1") (pinfunction "1_1") (pintype "passive"))
      (node (ref "R254") (pin "1") (pinfunction "1_1") (pintype "passive"))
      (node (ref "R255") (pin "2") (pinfunction "2_2") (pintype "passive"))
      (node (ref "R259") (pin "2") (pinfunction "2_2") (pintype "passive"))
      (node (ref "R260") (pin "1") (pinfunction "1_1") (pintype "passive"))
      (node (ref "R261") (pin "1") (pinfunction "1_1") (pintype "passive"))
      (node (ref "R262") (pin "1") (pinfunction "1_1") (pintype "passive"))
      (node (ref "R268") (pin "2") (pinfunction "2_2") (pintype "passive"))
      (node (ref "R269") (pin "1") (pinfunction "1_1") (pintype "passive"))
      (node (ref "R270") (pin "1") (pinfunction "1_1") (pintype "passive"))
      (node (ref "R646") (pin "1") (pinfunction "1_1") (pintype "passive"))
      (node (ref "R647") (pin "1") (pinfunction "1_1") (pintype "passive"))
      (node (ref "TP24") (pin "1") (pinfunction "1_1") (pintype "passive"))
      (node (ref "TP4") (pin "1") (pinfunction "1_1") (pintype "passive"))
      (node (ref "U23") (pin "8") (pinfunction "8_8") (pintype "passive"))
      (node (ref "U24") (pin "8") (pinfunction "8_8") (pintype "passive"))
      (node (ref "U25") (pin "8") (pinfunction "8_8") (pintype "passive"))
      (node (ref "U26") (pin "8") (pinfunction "8_8") (pintype "passive"))
      (node (ref "U27") (pin "8") (pinfunction "8_8") (pintype "passive"))
      (node (ref "U28") (pin "8") (pinfunction "8_8") (pintype "passive"))
      (node (ref "U29") (pin "8") (pinfunction "8_8") (pintype "passive"))
      (node (ref "U40") (pin "2") (pinfunction "GND_2") (pintype "passive"))
      (node (ref "VR2") (pin "1") (pinfunction "GND_1") (pintype "power_in"))
      (node (ref "VR3") (pin "1") (pinfunction "GND_1") (pintype "power_in"))
    )
    (net (code "16") (name "Net-(C137-Pad2)") (class "Default")
      (node (ref "C137") (pin "2") (pinfunction "2_2") (pintype "passive"))
      (node (ref "U23") (pin "10") (pinfunction "10_10") (pintype "passive"))
    )
    (net (code "17") (name "Net-(C138-Pad2)") (class "Default")
      (node (ref "C138") (pin "2") (pinfunction "2_2") (pintype "passive"))
      (node (ref "U23") (pin "7") (pinfunction "7_7") (pintype "passive"))
    )
    (net (code "18") (name "Net-(C145-Pad2)") (class "Default")
      (node (ref "C145") (pin "2") (pinfunction "2_2") (pintype "passive"))
      (node (ref "U24") (pin "10") (pinfunction "10_10") (pintype "passive"))
    )
    (net (code "19") (name "Net-(C146-Pad2)") (class "Default")
      (node (ref "C146") (pin "2") (pinfunction "2_2") (pintype "passive"))
      (node (ref "U24") (pin "7") (pinfunction "7_7") (pintype "passive"))
    )
    (net (code "20") (name "Net-(C153-Pad2)") (class "Default")
      (node (ref "C153") (pin "2") (pinfunction "2_2") (pintype "passive"))
      (node (ref "U25") (pin "10") (pinfunction "10_10") (pintype "passive"))
    )
    (net (code "21") (name "Net-(C154-Pad2)") (class "Default")
      (node (ref "C154") (pin "2") (pinfunction "2_2") (pintype "passive"))
      (node (ref "U25") (pin "7") (pinfunction "7_7") (pintype "passive"))
    )
    (net (code "22") (name "Net-(C155-Pad2)") (class "Default")
      (node (ref "C155") (pin "2") (pinfunction "2_2") (pintype "passive"))
      (node (ref "U26") (pin "10") (pinfunction "10_10") (pintype "passive"))
    )
    (net (code "23") (name "Net-(C156-Pad2)") (class "Default")
      (node (ref "C156") (pin "2") (pinfunction "2_2") (pintype "passive"))
      (node (ref "U26") (pin "7") (pinfunction "7_7") (pintype "passive"))
    )
    (net (code "24") (name "Net-(C166-Pad2)") (class "Default")
      (node (ref "C166") (pin "2") (pinfunction "2_2") (pintype "passive"))
      (node (ref "U27") (pin "10") (pinfunction "10_10") (pintype "passive"))
    )
    (net (code "25") (name "Net-(C167-Pad2)") (class "Default")
      (node (ref "C167") (pin "2") (pinfunction "2_2") (pintype "passive"))
      (node (ref "U27") (pin "7") (pinfunction "7_7") (pintype "passive"))
    )
    (net (code "26") (name "Net-(C168-Pad2)") (class "Default")
      (node (ref "C168") (pin "2") (pinfunction "2_2") (pintype "passive"))
      (node (ref "U28") (pin "10") (pinfunction "10_10") (pintype "passive"))
    )
    (net (code "27") (name "Net-(C169-Pad2)") (class "Default")
      (node (ref "C169") (pin "2") (pinfunction "2_2") (pintype "passive"))
      (node (ref "U28") (pin "7") (pinfunction "7_7") (pintype "passive"))
    )
    (net (code "28") (name "Net-(C173-Pad2)") (class "Default")
      (node (ref "C173") (pin "2") (pinfunction "2_2") (pintype "passive"))
      (node (ref "U29") (pin "10") (pinfunction "10_10") (pintype "passive"))
    )
    (net (code "29") (name "Net-(C174-Pad2)") (class "Default")
      (node (ref "C174") (pin "2") (pinfunction "2_2") (pintype "passive"))
      (node (ref "U29") (pin "7") (pinfunction "7_7") (pintype "passive"))
    )
    (net (code "30") (name "Net-(D42-K)") (class "Default")
      (node (ref "D42") (pin "1") (pinfunction "K_1") (pintype "passive"))
      (node (ref "R646") (pin "2") (pinfunction "2_2") (pintype "passive"))
    )
    (net (code "31") (name "Net-(D43-K)") (class "Default")
      (node (ref "D43") (pin "1") (pinfunction "K_1") (pintype "passive"))
      (node (ref "R647") (pin "2") (pinfunction "2_2") (pintype "passive"))
    )
    (net (code "32") (name "Net-(U23-EN{slash}UVLO)") (class "Default")
      (node (ref "R217") (pin "1") (pinfunction "1_1") (pintype "passive"))
      (node (ref "R220") (pin "2") (pinfunction "2_2") (pintype "passive"))
      (node (ref "U23") (pin "1") (pinfunction "EN/UVLO_1") (pintype "passive"))
    )
    (net (code "33") (name "Net-(U23-OVLO{slash}OVCSEL)") (class "Default")
      (node (ref "R220") (pin "1") (pinfunction "1_1") (pintype "passive"))
      (node (ref "R221") (pin "2") (pinfunction "2_2") (pintype "passive"))
      (node (ref "U23") (pin "2") (pinfunction "OVLO/OVCSEL_2") (pintype "passive"))
    )
    (net (code "34") (name "Net-(U23-PGTH{slash}~{FLT})") (class "Default")
      (node (ref "R219") (pin "1") (pinfunction "1_1") (pintype "passive"))
      (node (ref "U23") (pin "4") (pinfunction "PGTH/~{FLT}_4") (pintype "passive"))
    )
    (net (code "35") (name "Net-(U23-PG{slash}AUXOFF)") (class "Default")
      (node (ref "R218") (pin "1") (pinfunction "1_1") (pintype "passive"))
      (node (ref "U23") (pin "3") (pinfunction "PG/AUXOFF_3") (pintype "passive"))
    )
    (net (code "36") (name "Net-(U24-EN{slash}UVLO)") (class "Default")
      (node (ref "R225") (pin "1") (pinfunction "1_1") (pintype "passive"))
      (node (ref "R227") (pin "1") (pinfunction "1_1") (pintype "passive"))
      (node (ref "R229") (pin "1") (pinfunction "1_1") (pintype "passive"))
      (node (ref "U24") (pin "1") (pinfunction "EN/UVLO_1") (pintype "passive"))
    )
    (net (code "37") (name "Net-(U24-IN)") (class "Default")
      (node (ref "C141") (pin "2") (pinfunction "2_2") (pintype "passive"))
      (node (ref "JP4") (pin "2") (pinfunction "2_2") (pintype "passive"))
      (node (ref "JP5") (pin "2") (pinfunction "2_2") (pintype "passive"))
      (node (ref "JP6") (pin "1") (pinfunction "1_1") (pintype "passive"))
      (node (ref "R222") (pin "2") (pinfunction "2_2") (pintype "passive"))
      (node (ref "U24") (pin "5") (pinfunction "IN_5") (pintype "passive"))
    )
    (net (code "38") (name "Net-(U24-OVLO{slash}OVCSEL)") (class "Default")
      (node (ref "R222") (pin "1") (pinfunction "1_1") (pintype "passive"))
      (node (ref "R228") (pin "2") (pinfunction "2_2") (pintype "passive"))
      (node (ref "U24") (pin "2") (pinfunction "OVLO/OVCSEL_2") (pintype "passive"))
    )
    (net (code "39") (name "Net-(U24-PGTH{slash}~{FLT})") (class "Default")
      (node (ref "R224") (pin "1") (pinfunction "1_1") (pintype "passive"))
      (node (ref "U24") (pin "4") (pinfunction "PGTH/~{FLT}_4") (pintype "passive"))
    )
    (net (code "40") (name "Net-(U24-PG{slash}AUXOFF)") (class "Default")
      (node (ref "R223") (pin "1") (pinfunction "1_1") (pintype "passive"))
      (node (ref "U24") (pin "3") (pinfunction "PG/AUXOFF_3") (pintype "passive"))
    )
    (net (code "41") (name "Net-(U25-EN{slash}UVLO)") (class "Default")
      (node (ref "R237") (pin "1") (pinfunction "1_1") (pintype "passive"))
      (node (ref "R239") (pin "1") (pinfunction "1_1") (pintype "passive"))
      (node (ref "R243") (pin "1") (pinfunction "1_1") (pintype "passive"))
      (node (ref "U25") (pin "1") (pinfunction "EN/UVLO_1") (pintype "passive"))
    )
    (net (code "42") (name "Net-(U25-OVLO{slash}OVCSEL)") (class "Default")
      (node (ref "R231") (pin "1") (pinfunction "1_1") (pintype "passive"))
      (node (ref "R241") (pin "2") (pinfunction "2_2") (pintype "passive"))
      (node (ref "U25") (pin "2") (pinfunction "OVLO/OVCSEL_2") (pintype "passive"))
    )
    (net (code "43") (name "Net-(U25-PGTH{slash}~{FLT})") (class "Default")
      (node (ref "R234") (pin "1") (pinfunction "1_1") (pintype "passive"))
      (node (ref "U25") (pin "4") (pinfunction "PGTH/~{FLT}_4") (pintype "passive"))
    )
    (net (code "44") (name "Net-(U25-PG{slash}AUXOFF)") (class "Default")
      (node (ref "R233") (pin "1") (pinfunction "1_1") (pintype "passive"))
      (node (ref "U25") (pin "3") (pinfunction "PG/AUXOFF_3") (pintype "passive"))
    )
    (net (code "45") (name "Net-(U26-EN{slash}UVLO)") (class "Default")
      (node (ref "R238") (pin "1") (pinfunction "1_1") (pintype "passive"))
      (node (ref "R240") (pin "1") (pinfunction "1_1") (pintype "passive"))
      (node (ref "R244") (pin "1") (pinfunction "1_1") (pintype "passive"))
      (node (ref "U26") (pin "1") (pinfunction "EN/UVLO_1") (pintype "passive"))
    )
    (net (code "46") (name "Net-(U26-OVLO{slash}OVCSEL)") (class "Default")
      (node (ref "R232") (pin "1") (pinfunction "1_1") (pintype "passive"))
      (node (ref "R242") (pin "2") (pinfunction "2_2") (pintype "passive"))
      (node (ref "U26") (pin "2") (pinfunction "OVLO/OVCSEL_2") (pintype "passive"))
    )
    (net (code "47") (name "Net-(U26-PGTH{slash}~{FLT})") (class "Default")
      (node (ref "R236") (pin "1") (pinfunction "1_1") (pintype "passive"))
      (node (ref "U26") (pin "4") (pinfunction "PGTH/~{FLT}_4") (pintype "passive"))
    )
    (net (code "48") (name "Net-(U26-PG{slash}AUXOFF)") (class "Default")
      (node (ref "R235") (pin "1") (pinfunction "1_1") (pintype "passive"))
      (node (ref "U26") (pin "3") (pinfunction "PG/AUXOFF_3") (pintype "passive"))
    )
    (net (code "49") (name "Net-(U27-EN{slash}UVLO)") (class "Default")
      (node (ref "R250") (pin "1") (pinfunction "1_1") (pintype "passive"))
      (node (ref "R251") (pin "1") (pinfunction "1_1") (pintype "passive"))
      (node (ref "R255") (pin "1") (pinfunction "1_1") (pintype "passive"))
      (node (ref "U27") (pin "1") (pinfunction "EN/UVLO_1") (pintype "passive"))
    )
    (net (code "50") (name "Net-(U27-OVLO{slash}OVCSEL)") (class "Default")
      (node (ref "R247") (pin "1") (pinfunction "1_1") (pintype "passive"))
      (node (ref "R254") (pin "2") (pinfunction "2_2") (pintype "passive"))
      (node (ref "U27") (pin "2") (pinfunction "OVLO/OVCSEL_2") (pintype "passive"))
    )
    (net (code "51") (name "Net-(U27-PGTH{slash}~{FLT})") (class "Default")
      (node (ref "R249") (pin "1") (pinfunction "1_1") (pintype "passive"))
      (node (ref "U27") (pin "4") (pinfunction "PGTH/~{FLT}_4") (pintype "passive"))
    )
    (net (code "52") (name "Net-(U27-PG{slash}AUXOFF)") (class "Default")
      (node (ref "R248") (pin "1") (pinfunction "1_1") (pintype "passive"))
      (node (ref "U27") (pin "3") (pinfunction "PG/AUXOFF_3") (pintype "passive"))
    )
    (net (code "53") (name "Net-(U28-EN{slash}UVLO)") (class "Default")
      (node (ref "R252") (pin "1") (pinfunction "1_1") (pintype "passive"))
      (node (ref "R258") (pin "1") (pinfunction "1_1") (pintype "passive"))
      (node (ref "R259") (pin "1") (pinfunction "1_1") (pintype "passive"))
      (node (ref "U28") (pin "1") (pinfunction "EN/UVLO_1") (pintype "passive"))
    )
    (net (code "54") (name "Net-(U28-OVLO{slash}OVCSEL)") (class "Default")
      (node (ref "R253") (pin "1") (pinfunction "1_1") (pintype "passive"))
      (node (ref "R260") (pin "2") (pinfunction "2_2") (pintype "passive"))
      (node (ref "U28") (pin "2") (pinfunction "OVLO/OVCSEL_2") (pintype "passive"))
    )
    (net (code "55") (name "Net-(U28-PGTH{slash}~{FLT})") (class "Default")
      (node (ref "R257") (pin "1") (pinfunction "1_1") (pintype "passive"))
      (node (ref "U28") (pin "4") (pinfunction "PGTH/~{FLT}_4") (pintype "passive"))
    )
    (net (code "56") (name "Net-(U28-PG{slash}AUXOFF)") (class "Default")
      (node (ref "R256") (pin "1") (pinfunction "1_1") (pintype "passive"))
      (node (ref "U28") (pin "3") (pinfunction "PG/AUXOFF_3") (pintype "passive"))
    )
    (net (code "57") (name "Net-(U29-EN{slash}UVLO)") (class "Default")
      (node (ref "R263") (pin "1") (pinfunction "1_1") (pintype "passive"))
      (node (ref "R267") (pin "1") (pinfunction "1_1") (pintype "passive"))
      (node (ref "R268") (pin "1") (pinfunction "1_1") (pintype "passive"))
      (node (ref "U29") (pin "1") (pinfunction "EN/UVLO_1") (pintype "passive"))
    )
    (net (code "58") (name "Net-(U29-OVLO{slash}OVCSEL)") (class "Default")
      (node (ref "R264") (pin "1") (pinfunction "1_1") (pintype "passive"))
      (node (ref "R269") (pin "2") (pinfunction "2_2") (pintype "passive"))
      (node (ref "U29") (pin "2") (pinfunction "OVLO/OVCSEL_2") (pintype "passive"))
    )
    (net (code "59") (name "Net-(U29-PGTH{slash}~{FLT})") (class "Default")
      (node (ref "R266") (pin "1") (pinfunction "1_1") (pintype "passive"))
      (node (ref "U29") (pin "4") (pinfunction "PGTH/~{FLT}_4") (pintype "passive"))
    )
    (net (code "60") (name "Net-(U29-PG{slash}AUXOFF)") (class "Default")
      (node (ref "R265") (pin "1") (pinfunction "1_1") (pintype "passive"))
      (node (ref "U29") (pin "3") (pinfunction "PG/AUXOFF_3") (pintype "passive"))
    )
    (net (code "61") (name "Net-(U40-EN)") (class "Default")
      (node (ref "R295") (pin "1") (pinfunction "1_1") (pintype "passive"))
      (node (ref "U40") (pin "3") (pinfunction "EN_3") (pintype "passive"))
    )
    (net (code "62") (name "POW_ONOFF_5V") (class "Default")
      (node (ref "R237") (pin "2") (pinfunction "2_2") (pintype "passive"))
    )
    (net (code "63") (name "POW_ONOFF_HD4") (class "Default")
      (node (ref "R267") (pin "2") (pinfunction "2_2") (pintype "passive"))
    )
    (net (code "64") (name "POW_ONOFF_Laser") (class "Default")
      (node (ref "R250") (pin "2") (pinfunction "2_2") (pintype "passive"))
    )
    (net (code "65") (name "POW_ONOFF_Photo") (class "Default")
      (node (ref "R238") (pin "2") (pinfunction "2_2") (pintype "passive"))
    )
    (net (code "66") (name "POW_ONOFF_Solenoid") (class "Default")
      (node (ref "R225") (pin "2") (pinfunction "2_2") (pintype "passive"))
    )
    (net (code "67") (name "POW_ONOFF_TEC") (class "Default")
      (node (ref "R258") (pin "2") (pinfunction "2_2") (pintype "passive"))
    )
    (net (code "68") (name "eFUSE_ILIM_3{slash}5V_Solenoid") (class "Default")
      (node (ref "R230") (pin "2") (pinfunction "2_2") (pintype "passive"))
      (node (ref "U24") (pin "9") (pinfunction "9_9") (pintype "passive"))
    )
    (net (code "69") (name "eFUSE_ILIM_5V") (class "Default")
      (node (ref "R245") (pin "2") (pinfunction "2_2") (pintype "passive"))
      (node (ref "U25") (pin "9") (pinfunction "9_9") (pintype "passive"))
    )
    (net (code "70") (name "eFUSE_ILIM_5V_HD4") (class "Default")
      (node (ref "R270") (pin "2") (pinfunction "2_2") (pintype "passive"))
      (node (ref "U29") (pin "9") (pinfunction "9_9") (pintype "passive"))
    )
    (net (code "71") (name "eFUSE_ILIM_5V_MCU") (class "Default")
      (node (ref "R226") (pin "2") (pinfunction "2_2") (pintype "passive"))
      (node (ref "U23") (pin "9") (pinfunction "9_9") (pintype "passive"))
    )
    (net (code "72") (name "eFUSE_ILIM_5V_TEC") (class "Default")
      (node (ref "R262") (pin "2") (pinfunction "2_2") (pintype "passive"))
      (node (ref "U28") (pin "9") (pinfunction "9_9") (pintype "passive"))
    )
    (net (code "73") (name "eFUSE_ILIM_12V_Laser") (class "Default")
      (node (ref "R261") (pin "2") (pinfunction "2_2") (pintype "passive"))
      (node (ref "U27") (pin "9") (pinfunction "9_9") (pintype "passive"))
    )
    (net (code "74") (name "eFUSE_ILIM_12V_Photo") (class "Default")
      (node (ref "R246") (pin "2") (pinfunction "2_2") (pintype "passive"))
      (node (ref "U26") (pin "9") (pinfunction "9_9") (pintype "passive"))
    )
    (net (code "75") (name "unconnected-(U40-NC-Pad4)") (class "Default")
      (node (ref "U40") (pin "4") (pinfunction "NC_4") (pintype "passive+no_connect"))
    )
  )
)
